# CH6_IMU_and_GPS.net
KiCad netlist of a schematic drawn in EAGLE
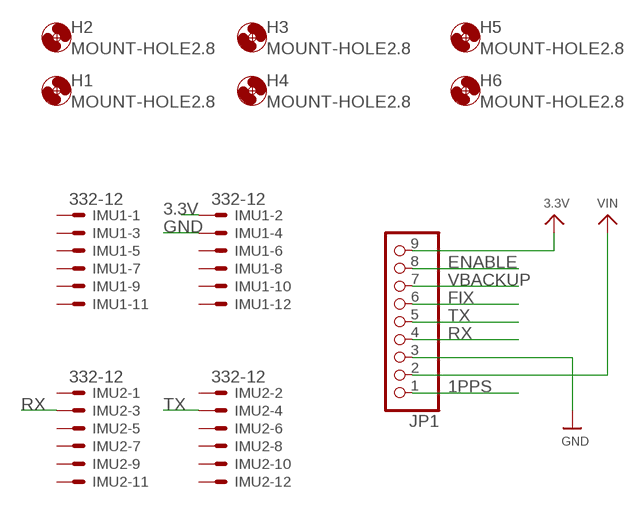
[diagram p0: schematic, sheet 1]

(export (version "E")
  (design (tool "Eeschema 10.0.6"))
  (components
    (comp (ref "H1")
      (value "MOUNT-HOLE2.8")
      (footprint "eagle-import:2,8")
      (libsource (lib "eagle-import") (part "MOUNT-HOLE2.8"))
    )
    (comp (ref "H2")
      (value "MOUNT-HOLE2.8")
      (footprint "eagle-import:2,8")
      (libsource (lib "eagle-import") (part "MOUNT-HOLE2.8"))
    )
    (comp (ref "H3")
      (value "MOUNT-HOLE2.8")
      (footprint "eagle-import:2,8")
      (libsource (lib "eagle-import") (part "MOUNT-HOLE2.8"))
    )
    (comp (ref "H4")
      (value "MOUNT-HOLE2.8")
      (footprint "eagle-import:2,8")
      (libsource (lib "eagle-import") (part "MOUNT-HOLE2.8"))
    )
    (comp (ref "H5")
      (value "MOUNT-HOLE2.8")
      (footprint "eagle-import:2,8")
      (libsource (lib "eagle-import") (part "MOUNT-HOLE2.8"))
    )
    (comp (ref "H6")
      (value "MOUNT-HOLE2.8")
      (footprint "eagle-import:2,8")
      (libsource (lib "eagle-import") (part "MOUNT-HOLE2.8"))
    )
    (comp (ref "IMU1")
      (value "332-12")
      (footprint "eagle-import:332-12")
      (libsource (lib "eagle-import") (part "332-12"))
    )
    (comp (ref "IMU2")
      (value "332-12")
      (footprint "eagle-import:332-12")
      (libsource (lib "eagle-import") (part "332-12"))
    )
    (comp (ref "JP1")
      (value "HEADER-1X970MIL")
      (footprint "eagle-import:1X09_ROUND_70")
      (libsource (lib "eagle-import") (part "HEADER-1X970MIL"))
    )
  )
  (nets
    (net (code "1") (name "/1PPS") (class "Default")
      (node (ref "JP1") (pin "1") (pinfunction "1_1") (pintype "passive"))
    )
    (net (code "2") (name "/ENABLE") (class "Default")
      (node (ref "JP1") (pin "8") (pinfunction "8_8") (pintype "passive"))
    )
    (net (code "3") (name "/FIX") (class "Default")
      (node (ref "JP1") (pin "6") (pinfunction "6_6") (pintype "passive"))
    )
    (net (code "4") (name "/RX") (class "Default")
      (node (ref "IMU2") (pin "3") (pinfunction "S_3") (pintype "passive"))
      (node (ref "JP1") (pin "4") (pinfunction "4_4") (pintype "passive"))
    )
    (net (code "5") (name "/TX") (class "Default")
      (node (ref "IMU2") (pin "4") (pinfunction "S_4") (pintype "passive"))
      (node (ref "JP1") (pin "5") (pinfunction "5_5") (pintype "passive"))
    )
    (net (code "6") (name "/VBACKUP") (class "Default")
      (node (ref "JP1") (pin "7") (pinfunction "7_7") (pintype "passive"))
    )
    (net (code "7") (name "3.3V") (class "Default")
      (node (ref "IMU1") (pin "2") (pinfunction "S_2") (pintype "passive"))
      (node (ref "JP1") (pin "9") (pinfunction "9_9") (pintype "passive"))
    )
    (net (code "8") (name "GND") (class "Default")
      (node (ref "IMU1") (pin "4") (pinfunction "S_4") (pintype "passive"))
      (node (ref "JP1") (pin "3") (pinfunction "3_3") (pintype "passive"))
    )
    (net (code "9") (name "VIN") (class "Default")
      (node (ref "JP1") (pin "2") (pinfunction "2_2") (pintype "passive"))
    )
    (net (code "10") (name "unconnected-(IMU1A-S-Pad1)") (class "Default")
      (node (ref "IMU1") (pin "1") (pinfunction "S_1") (pintype "passive"))
    )
    (net (code "11") (name "unconnected-(IMU1B-S-Pad10)") (class "Default")
      (node (ref "IMU1") (pin "10") (pinfunction "S_10") (pintype "passive"))
    )
    (net (code "12") (name "unconnected-(IMU1C-S-Pad11)") (class "Default")
      (node (ref "IMU1") (pin "11") (pinfunction "S_11") (pintype "passive"))
    )
    (net (code "13") (name "unconnected-(IMU1D-S-Pad12)") (class "Default")
      (node (ref "IMU1") (pin "12") (pinfunction "S_12") (pintype "passive"))
    )
    (net (code "14") (name "unconnected-(IMU1F-S-Pad3)") (class "Default")
      (node (ref "IMU1") (pin "3") (pinfunction "S_3") (pintype "passive"))
    )
    (net (code "15") (name "unconnected-(IMU1H-S-Pad5)") (class "Default")
      (node (ref "IMU1") (pin "5") (pinfunction "S_5") (pintype "passive"))
    )
    (net (code "16") (name "unconnected-(IMU1I-S-Pad6)") (class "Default")
      (node (ref "IMU1") (pin "6") (pinfunction "S_6") (pintype "passive"))
    )
    (net (code "17") (name "unconnected-(IMU1J-S-Pad7)") (class "Default")
      (node (ref "IMU1") (pin "7") (pinfunction "S_7") (pintype "passive"))
    )
    (net (code "18") (name "unconnected-(IMU1K-S-Pad8)") (class "Default")
      (node (ref "IMU1") (pin "8") (pinfunction "S_8") (pintype "passive"))
    )
    (net (code "19") (name "unconnected-(IMU1L-S-Pad9)") (class "Default")
      (node (ref "IMU1") (pin "9") (pinfunction "S_9") (pintype "passive"))
    )
    (net (code "20") (name "unconnected-(IMU2A-S-Pad1)") (class "Default")
      (node (ref "IMU2") (pin "1") (pinfunction "S_1") (pintype "passive"))
    )
    (net (code "21") (name "unconnected-(IMU2B-S-Pad10)") (class "Default")
      (node (ref "IMU2") (pin "10") (pinfunction "S_10") (pintype "passive"))
    )
    (net (code "22") (name "unconnected-(IMU2C-S-Pad11)") (class "Default")
      (node (ref "IMU2") (pin "11") (pinfunction "S_11") (pintype "passive"))
    )
    (net (code "23") (name "unconnected-(IMU2D-S-Pad12)") (class "Default")
      (node (ref "IMU2") (pin "12") (pinfunction "S_12") (pintype "passive"))
    )
    (net (code "24") (name "unconnected-(IMU2E-S-Pad2)") (class "Default")
      (node (ref "IMU2") (pin "2") (pinfunction "S_2") (pintype "passive"))
    )
    (net (code "25") (name "unconnected-(IMU2H-S-Pad5)") (class "Default")
      (node (ref "IMU2") (pin "5") (pinfunction "S_5") (pintype "passive"))
    )
    (net (code "26") (name "unconnected-(IMU2I-S-Pad6)") (class "Default")
      (node (ref "IMU2") (pin "6") (pinfunction "S_6") (pintype "passive"))
    )
    (net (code "27") (name "unconnected-(IMU2J-S-Pad7)") (class "Default")
      (node (ref "IMU2") (pin "7") (pinfunction "S_7") (pintype "passive"))
    )
    (net (code "28") (name "unconnected-(IMU2K-S-Pad8)") (class "Default")
      (node (ref "IMU2") (pin "8") (pinfunction "S_8") (pintype "passive"))
    )
    (net (code "29") (name "unconnected-(IMU2L-S-Pad9)") (class "Default")
      (node (ref "IMU2") (pin "9") (pinfunction "S_9") (pintype "passive"))
    )
  )
)
